# Unit_de_traitement.net
KiCad netlist of a schematic drawn in Altium Designer
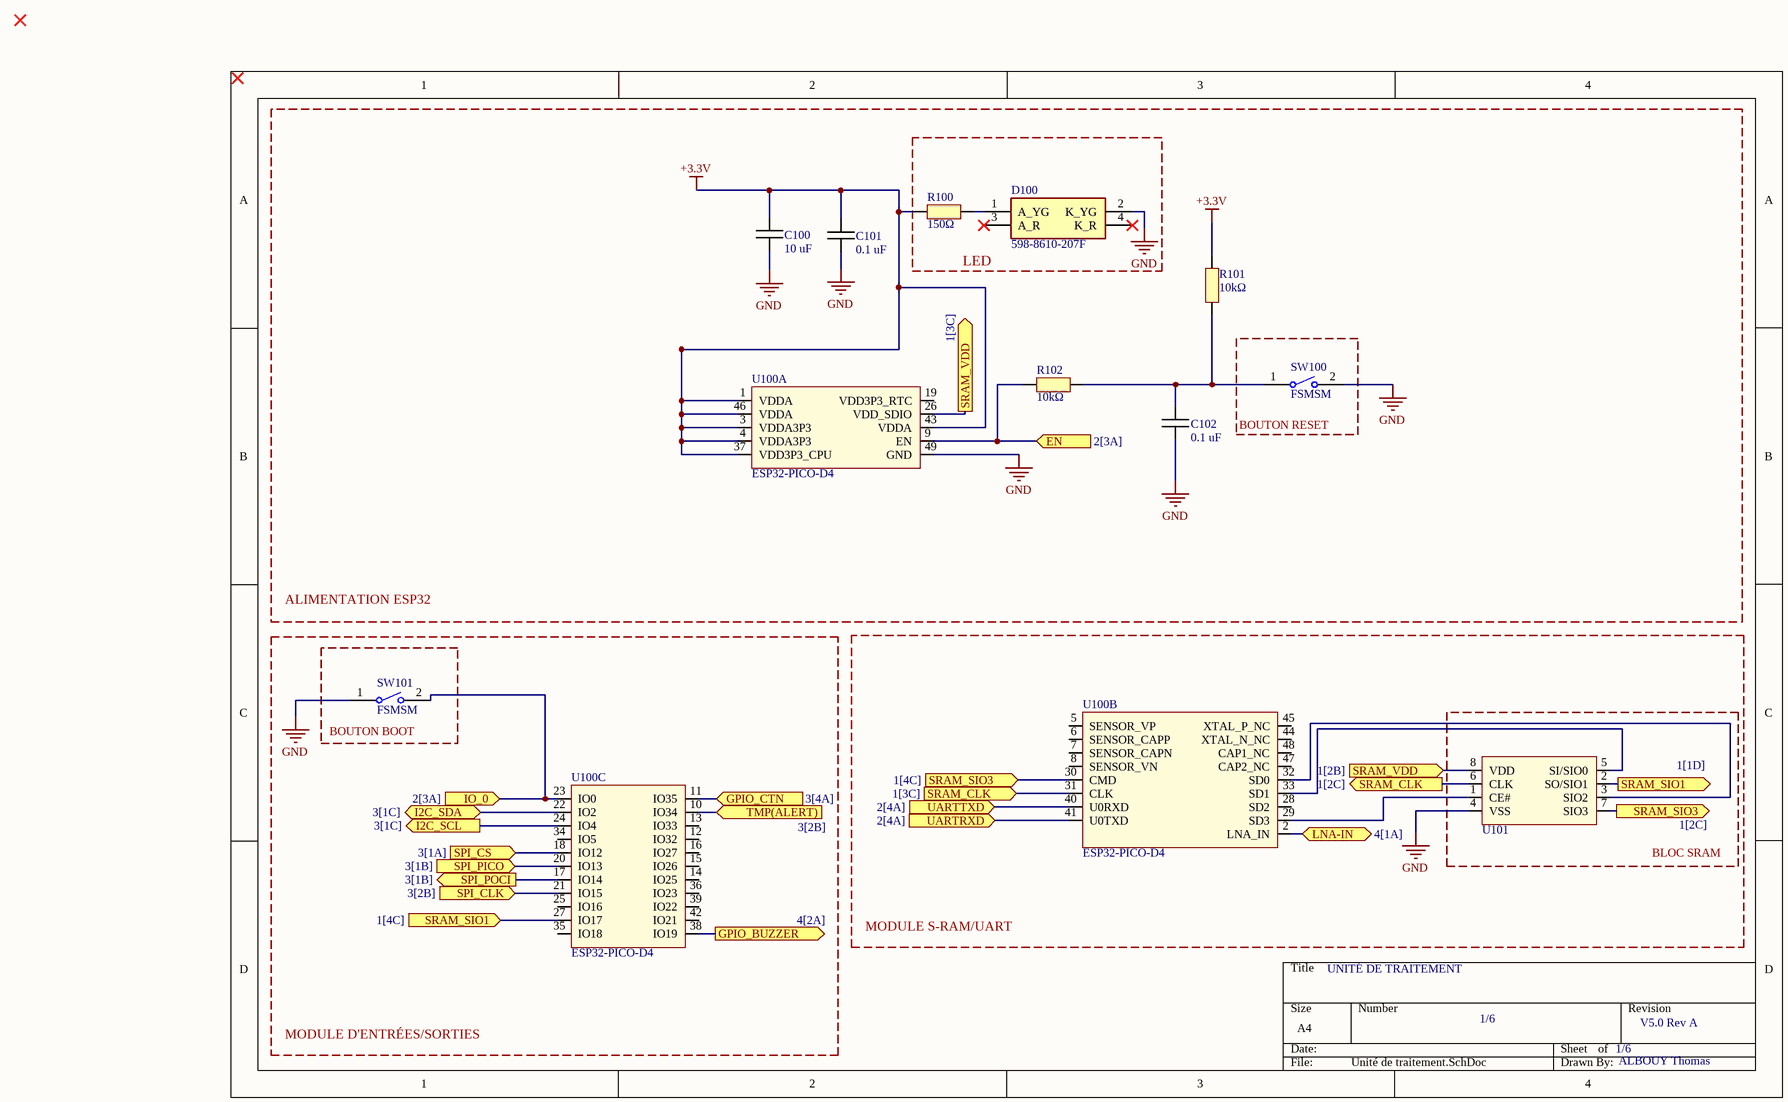
[diagram p0: Unité de traitement.SchDoc]

(export (version "E")
  (design (tool "Eeschema 10.0.6"))
  (components
    (comp (ref "C100")
      (value "10 uF")
      (footprint "CAPC1005X06N")
      (libsource (lib "SCHLibrary") (part "Capacitor"))
    )
    (comp (ref "C101")
      (value "0.1 uF")
      (footprint "CAPC1005X06N")
      (libsource (lib "SCHLibrary") (part "Capacitor"))
    )
    (comp (ref "C102")
      (value "0.1 uF")
      (footprint "CAPC1005X06N")
      (libsource (lib "SCHLibrary") (part "Capacitor"))
    )
    (comp (ref "D100")
      (value "598-8610-207F")
      (footprint "5988610207F")
      (description "Standard LEDs - SMD Red/Green WC 80/50mcd 645/570nm")
      (fields (field (name "MOUSER PART NUMBER") "645-598-8610-207F"))
      (libsource (lib "SCHLibrary") (part "598-8610-207F"))
    )
    (comp (ref "R100")
      (value "150Ω")
      (footprint "RESC1005X06N")
      (libsource (lib "SCHLibrary") (part "Resistor"))
    )
    (comp (ref "R101") (value "10kΩ") (footprint "RESC1005X06N") (libsource (lib "") (part "Resistor_1")))
    (comp (ref "R102")
      (value "10kΩ")
      (footprint "RESC1005X06N")
      (libsource (lib "SCHLibrary") (part "Resistor"))
    )
    (comp (ref "SW100")
      (value "FSMSM")
      (footprint "TECO-FSMSM-2_V")
      (description "FSMSM Push Button Switch, 50 mA, -35 to 85 degC, 2-Pin SMD, RoHS, Bulk")
      (fields (field (name "MANUFACTURER") "TE Connectivity"))
      (libsource (lib "SCHLibrary") (part "CMP-2000-07511-1"))
    )
    (comp (ref "SW101")
      (value "FSMSM")
      (footprint "TECO-FSMSM-2_V")
      (description "FSMSM Push Button Switch, 50 mA, -35 to 85 degC, 2-Pin SMD, RoHS, Bulk")
      (fields (field (name "MANUFACTURER") "TE Connectivity"))
      (libsource (lib "SCHLibrary") (part "CMP-2000-07511-1"))
    )
    (comp (ref "U100")
      (value "ESP32-PICO-D4")
      (footprint "PQFN50P700X700X104_HS-49N")
      (libsource (lib "SCHLibrary") (part "ESP32"))
    )
    (comp (ref "U101")
      (value "IS66WVS1M8BLL-104NLI")
      (footprint "SOIC127P600X175-8N")
      (description "SRAM 8Mb, SerialRAM, 2.7V-3.6V, 104MHz, 8 pin SOIC 150 mil, RoHS")
      (libsource (lib "SCHLibrary") (part "SRAM"))
    )
  )
  (nets
    (net (code "1") (name "+3.3V") (class "Default")
      (node (ref "C100") (pin "1") (pinfunction "1_1") (pintype "passive"))
      (node (ref "C101") (pin "1") (pinfunction "1_1") (pintype "passive"))
      (node (ref "R100") (pin "1") (pinfunction "1_1") (pintype "passive"))
      (node (ref "R101") (pin "2") (pinfunction "2_2") (pintype "passive"))
      (node (ref "U100") (pin "1") (pinfunction "VDDA_1") (pintype "passive"))
      (node (ref "U100") (pin "3") (pinfunction "VDDA3P3_3") (pintype "passive"))
      (node (ref "U100") (pin "37") (pinfunction "VDD3P3_CPU_37") (pintype "passive"))
      (node (ref "U100") (pin "4") (pinfunction "VDDA3P3_4") (pintype "passive"))
      (node (ref "U100") (pin "43") (pinfunction "VDDA_43") (pintype "passive"))
      (node (ref "U100") (pin "46") (pinfunction "VDDA_46") (pintype "passive"))
    )
    (net (code "2") (name "/EN") (class "Default")
      (node (ref "R102") (pin "1") (pinfunction "1_1") (pintype "passive"))
      (node (ref "U100") (pin "9") (pinfunction "EN_9") (pintype "passive"))
    )
    (net (code "3") (name "/GPIO_BUZZER") (class "Default")
      (node (ref "U100") (pin "38") (pinfunction "IO19_38") (pintype "passive"))
    )
    (net (code "4") (name "/GPIO_CTN") (class "Default")
      (node (ref "U100") (pin "11") (pinfunction "IO35_11") (pintype "passive"))
    )
    (net (code "5") (name "/I2C_SCL") (class "Default")
      (node (ref "U100") (pin "24") (pinfunction "IO4_24") (pintype "passive"))
    )
    (net (code "6") (name "/I2C_SDA") (class "Default")
      (node (ref "U100") (pin "22") (pinfunction "IO2_22") (pintype "passive"))
    )
    (net (code "7") (name "/IO_0") (class "Default")
      (node (ref "SW101") (pin "2") (pinfunction "2_2") (pintype "passive"))
      (node (ref "U100") (pin "23") (pinfunction "IO0_23") (pintype "passive"))
    )
    (net (code "8") (name "/LNA-IN") (class "Default")
      (node (ref "U100") (pin "2") (pinfunction "LNA_IN_2") (pintype "passive"))
    )
    (net (code "9") (name "/SPI_CLK") (class "Default")
      (node (ref "U100") (pin "21") (pinfunction "IO15_21") (pintype "passive"))
    )
    (net (code "10") (name "/SPI_CS") (class "Default")
      (node (ref "U100") (pin "18") (pinfunction "IO12_18") (pintype "passive"))
    )
    (net (code "11") (name "/SPI_PICO") (class "Default")
      (node (ref "U100") (pin "20") (pinfunction "IO13_20") (pintype "passive"))
    )
    (net (code "12") (name "/SPI_POCI") (class "Default")
      (node (ref "U100") (pin "17") (pinfunction "IO14_17") (pintype "passive"))
    )
    (net (code "13") (name "/SRAM_CLK") (class "Default")
      (node (ref "U100") (pin "31") (pinfunction "CLK_31") (pintype "passive"))
      (node (ref "U101") (pin "6") (pinfunction "CLK_6") (pintype "passive"))
    )
    (net (code "14") (name "/SRAM_SIO1") (class "Default")
      (node (ref "U100") (pin "27") (pinfunction "IO17_27") (pintype "passive"))
      (node (ref "U101") (pin "2") (pinfunction "SO/SIO1_2") (pintype "passive"))
    )
    (net (code "15") (name "/SRAM_SIO3") (class "Default")
      (node (ref "U100") (pin "30") (pinfunction "CMD_30") (pintype "passive"))
      (node (ref "U101") (pin "7") (pinfunction "SIO3_7") (pintype "passive"))
    )
    (net (code "16") (name "/SRAM_VDD") (class "Default")
      (node (ref "U100") (pin "26") (pinfunction "VDD_SDIO_26") (pintype "passive"))
      (node (ref "U101") (pin "8") (pinfunction "VDD_8") (pintype "passive"))
    )
    (net (code "17") (name "/TMP(ALERT)") (class "Default")
      (node (ref "U100") (pin "10") (pinfunction "IO34_10") (pintype "passive"))
    )
    (net (code "18") (name "/UARTRXD") (class "Default")
      (node (ref "U100") (pin "41") (pinfunction "U0TXD_41") (pintype "passive"))
    )
    (net (code "19") (name "/UARTTXD") (class "Default")
      (node (ref "U100") (pin "40") (pinfunction "U0RXD_40") (pintype "passive"))
    )
    (net (code "20") (name "GND") (class "Default")
      (node (ref "C100") (pin "2") (pinfunction "2_2") (pintype "passive"))
      (node (ref "C101") (pin "2") (pinfunction "2_2") (pintype "passive"))
      (node (ref "C102") (pin "2") (pinfunction "2_2") (pintype "passive"))
      (node (ref "D100") (pin "2") (pinfunction "K_YG_2") (pintype "passive"))
      (node (ref "SW100") (pin "2") (pinfunction "2_2") (pintype "passive"))
      (node (ref "SW101") (pin "1") (pinfunction "1_1") (pintype "passive"))
      (node (ref "U100") (pin "49") (pinfunction "GND_49") (pintype "passive"))
      (node (ref "U101") (pin "4") (pinfunction "VSS_4") (pintype "passive"))
    )
    (net (code "21") (name "Net-(C102-Pad1)") (class "Default")
      (node (ref "C102") (pin "1") (pinfunction "1_1") (pintype "passive"))
      (node (ref "R101") (pin "1") (pinfunction "1_1") (pintype "passive"))
      (node (ref "R102") (pin "2") (pinfunction "2_2") (pintype "passive"))
      (node (ref "SW100") (pin "1") (pinfunction "1_1") (pintype "passive"))
    )
    (net (code "22") (name "Net-(D100-A_YG)") (class "Default")
      (node (ref "D100") (pin "1") (pinfunction "A_YG_1") (pintype "passive"))
      (node (ref "R100") (pin "2") (pinfunction "2_2") (pintype "passive"))
    )
    (net (code "23") (name "Net-(U100B-SD0)") (class "Default")
      (node (ref "U100") (pin "32") (pinfunction "SD0_32") (pintype "passive"))
      (node (ref "U101") (pin "3") (pinfunction "SIO2_3") (pintype "passive"))
    )
    (net (code "24") (name "Net-(U100B-SD1)") (class "Default")
      (node (ref "U100") (pin "33") (pinfunction "SD1_33") (pintype "passive"))
      (node (ref "U101") (pin "5") (pinfunction "SI/SIO0_5") (pintype "passive"))
    )
    (net (code "25") (name "Net-(U100B-SD3)") (class "Default")
      (node (ref "U100") (pin "29") (pinfunction "SD3_29") (pintype "passive"))
      (node (ref "U101") (pin "1") (pinfunction "CE#_1") (pintype "passive"))
    )
    (net (code "26") (name "unconnected-(D100-A_R-Pad3)") (class "Default")
      (node (ref "D100") (pin "3") (pinfunction "A_R_3") (pintype "passive+no_connect"))
    )
    (net (code "27") (name "unconnected-(D100-K_R-Pad4)") (class "Default")
      (node (ref "D100") (pin "4") (pinfunction "K_R_4") (pintype "passive+no_connect"))
    )
    (net (code "28") (name "unconnected-(U100A-VDD3P3_RTC-Pad19)") (class "Default")
      (node (ref "U100") (pin "19") (pinfunction "VDD3P3_RTC_19") (pintype "passive"))
    )
    (net (code "29") (name "unconnected-(U100B-CAP1_NC-Pad48)") (class "Default")
      (node (ref "U100") (pin "48") (pinfunction "CAP1_NC_48") (pintype "passive"))
    )
    (net (code "30") (name "unconnected-(U100B-CAP2_NC-Pad47)") (class "Default")
      (node (ref "U100") (pin "47") (pinfunction "CAP2_NC_47") (pintype "passive"))
    )
    (net (code "31") (name "unconnected-(U100B-SD2-Pad28)") (class "Default")
      (node (ref "U100") (pin "28") (pinfunction "SD2_28") (pintype "passive"))
    )
    (net (code "32") (name "unconnected-(U100B-SENSOR_CAPN-Pad7)") (class "Default")
      (node (ref "U100") (pin "7") (pinfunction "SENSOR_CAPN_7") (pintype "passive"))
    )
    (net (code "33") (name "unconnected-(U100B-SENSOR_CAPP-Pad6)") (class "Default")
      (node (ref "U100") (pin "6") (pinfunction "SENSOR_CAPP_6") (pintype "passive"))
    )
    (net (code "34") (name "unconnected-(U100B-SENSOR_VN-Pad8)") (class "Default")
      (node (ref "U100") (pin "8") (pinfunction "SENSOR_VN_8") (pintype "passive"))
    )
    (net (code "35") (name "unconnected-(U100B-SENSOR_VP-Pad5)") (class "Default")
      (node (ref "U100") (pin "5") (pinfunction "SENSOR_VP_5") (pintype "passive"))
    )
    (net (code "36") (name "unconnected-(U100B-XTAL_N_NC-Pad44)") (class "Default")
      (node (ref "U100") (pin "44") (pinfunction "XTAL_N_NC_44") (pintype "passive"))
    )
    (net (code "37") (name "unconnected-(U100B-XTAL_P_NC-Pad45)") (class "Default")
      (node (ref "U100") (pin "45") (pinfunction "XTAL_P_NC_45") (pintype "passive"))
    )
    (net (code "38") (name "unconnected-(U100C-IO5-Pad34)") (class "Default")
      (node (ref "U100") (pin "34") (pinfunction "IO5_34") (pintype "passive"))
    )
    (net (code "39") (name "unconnected-(U100C-IO16-Pad25)") (class "Default")
      (node (ref "U100") (pin "25") (pinfunction "IO16_25") (pintype "passive"))
    )
    (net (code "40") (name "unconnected-(U100C-IO18-Pad35)") (class "Default")
      (node (ref "U100") (pin "35") (pinfunction "IO18_35") (pintype "passive"))
    )
    (net (code "41") (name "unconnected-(U100C-IO21-Pad42)") (class "Default")
      (node (ref "U100") (pin "42") (pinfunction "IO21_42") (pintype "passive"))
    )
    (net (code "42") (name "unconnected-(U100C-IO22-Pad39)") (class "Default")
      (node (ref "U100") (pin "39") (pinfunction "IO22_39") (pintype "passive"))
    )
    (net (code "43") (name "unconnected-(U100C-IO23-Pad36)") (class "Default")
      (node (ref "U100") (pin "36") (pinfunction "IO23_36") (pintype "passive"))
    )
    (net (code "44") (name "unconnected-(U100C-IO25-Pad14)") (class "Default")
      (node (ref "U100") (pin "14") (pinfunction "IO25_14") (pintype "passive"))
    )
    (net (code "45") (name "unconnected-(U100C-IO26-Pad15)") (class "Default")
      (node (ref "U100") (pin "15") (pinfunction "IO26_15") (pintype "passive"))
    )
    (net (code "46") (name "unconnected-(U100C-IO27-Pad16)") (class "Default")
      (node (ref "U100") (pin "16") (pinfunction "IO27_16") (pintype "passive"))
    )
    (net (code "47") (name "unconnected-(U100C-IO32-Pad12)") (class "Default")
      (node (ref "U100") (pin "12") (pinfunction "IO32_12") (pintype "passive"))
    )
    (net (code "48") (name "unconnected-(U100C-IO33-Pad13)") (class "Default")
      (node (ref "U100") (pin "13") (pinfunction "IO33_13") (pintype "passive"))
    )
  )
)
